# AR_-_Attack_Release.net
KiCad netlist of a schematic drawn in EAGLE
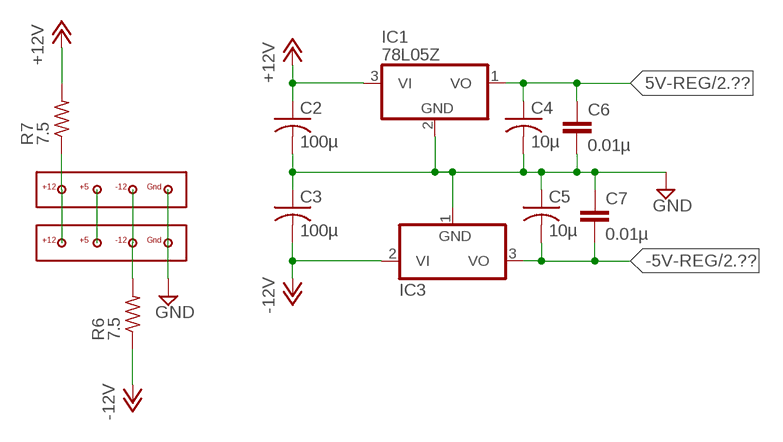
[diagram p0: schematic, sheet 1]
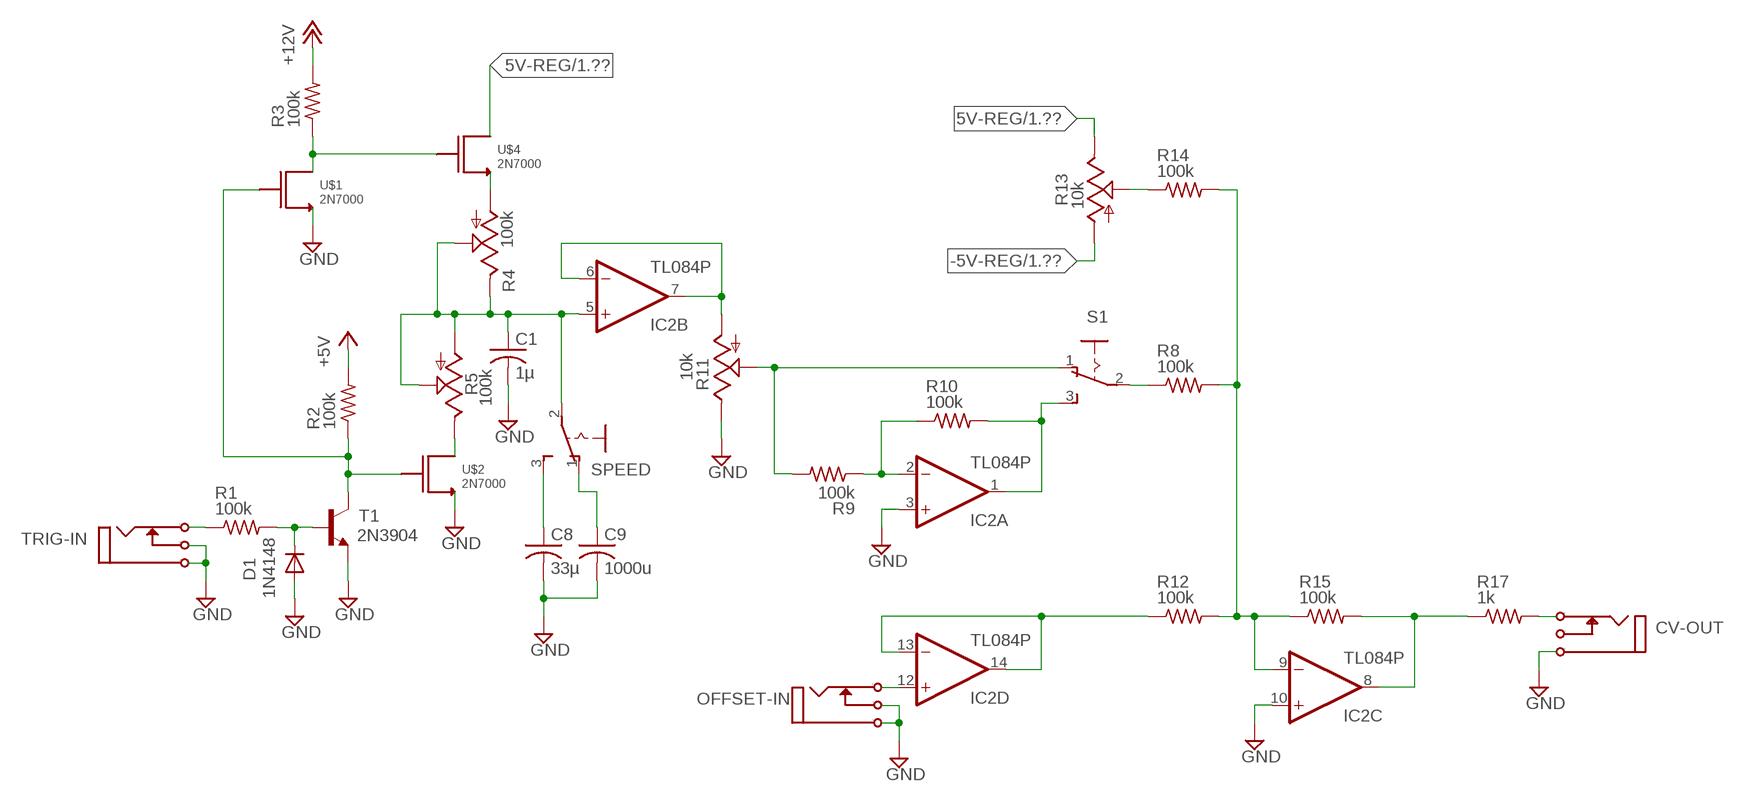
[diagram p1: schematic, sheet 2]
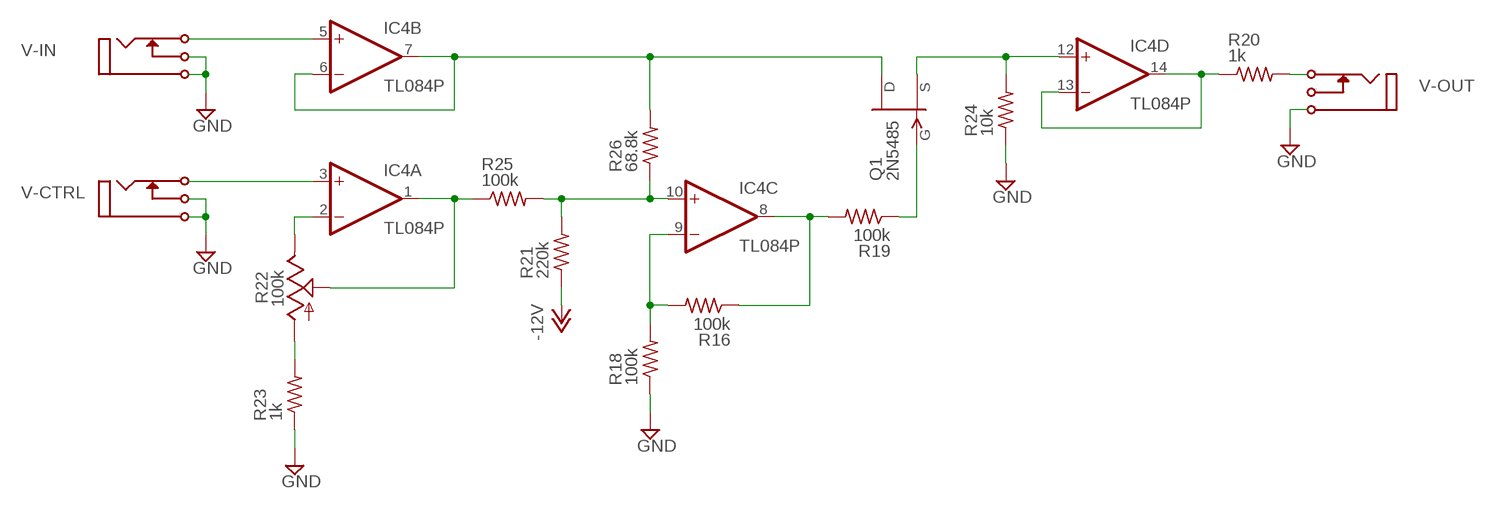
[diagram p2: schematic, sheet 3]

(export (version "E")
  (design (tool "Eeschema 10.0.6"))
  (components
    (comp (ref "C2")
      (value "100µ")
      (footprint "eagle-import:C025-050X050")
      (libsource (lib "eagle-import") (part "C-US025-050X050"))
    )
    (comp (ref "C3")
      (value "100µ")
      (footprint "eagle-import:C025-050X050")
      (libsource (lib "eagle-import") (part "C-US025-050X050"))
    )
    (comp (ref "C4")
      (value "10µ")
      (footprint "eagle-import:C025-050X050")
      (libsource (lib "eagle-import") (part "C-US025-050X050"))
    )
    (comp (ref "C5")
      (value "10µ")
      (footprint "eagle-import:C025-050X050")
      (libsource (lib "eagle-import") (part "C-US025-050X050"))
    )
    (comp (ref "C6")
      (value "0.01µ")
      (footprint "eagle-import:C2.5-2")
      (libsource (lib "eagle-import") (part "C2.5/2"))
    )
    (comp (ref "C7")
      (value "0.01µ")
      (footprint "eagle-import:C2.5-2")
      (libsource (lib "eagle-import") (part "C2.5/2"))
    )
    (comp (ref "IC1")
      (value "78L05Z")
      (footprint "eagle-import:TO92")
      (libsource (lib "eagle-import") (part "78ZL05"))
    )
    (comp (ref "IC3")
      (value "79L05Z")
      (footprint "eagle-import:TO92")
      (libsource (lib "eagle-import") (part "79ZL05"))
    )
    (comp (ref "R6")
      (value "7.5")
      (footprint "eagle-import:0204_7")
      (libsource (lib "eagle-import") (part "R-US_0204/7"))
    )
    (comp (ref "R7")
      (value "7.5")
      (footprint "eagle-import:0204_7")
      (libsource (lib "eagle-import") (part "R-US_0204/7"))
    )
    (comp (ref "U$3")
      (value "POWER_CONNECTOR_4_RGBB")
      (footprint "eagle-import:POWER_CONNECTOR_4_RGBB")
      (libsource (lib "eagle-import") (part "POWER_CONNECTOR_4_RGBB"))
    )
    (comp (ref "U$7")
      (value "POWER_CONNECTOR_4_RGBB")
      (footprint "eagle-import:POWER_CONNECTOR_4_RGBB")
      (libsource (lib "eagle-import") (part "POWER_CONNECTOR_4_RGBB"))
    )
    (comp (ref "IC4")
      (value "TL084P")
      (footprint "eagle-import:DIL14")
      (libsource (lib "eagle-import") (part "TL084P"))
    )
    (comp (ref "Q1")
      (value "2N5485")
      (footprint "eagle-import:TO92-")
      (libsource (lib "eagle-import") (part "?5482N5"))
    )
    (comp (ref "R16")
      (value "100k")
      (footprint "eagle-import:0204_7")
      (libsource (lib "eagle-import") (part "R-US_0204/7"))
    )
    (comp (ref "R18")
      (value "100k")
      (footprint "eagle-import:0204_7")
      (libsource (lib "eagle-import") (part "R-US_0204/7"))
    )
    (comp (ref "R19")
      (value "100k")
      (footprint "eagle-import:0204_7")
      (libsource (lib "eagle-import") (part "R-US_0204/7"))
    )
    (comp (ref "R20")
      (value "1k")
      (footprint "eagle-import:0204_7")
      (libsource (lib "eagle-import") (part "R-US_0204/7"))
    )
    (comp (ref "R21")
      (value "220k")
      (footprint "eagle-import:0204_7")
      (libsource (lib "eagle-import") (part "R-US_0204/7"))
    )
    (comp (ref "R22")
      (value "100k")
      (footprint "eagle-import:B64Y")
      (libsource (lib "eagle-import") (part "TRIM_US-B64Y"))
    )
    (comp (ref "R23")
      (value "1k")
      (footprint "eagle-import:0204_7")
      (libsource (lib "eagle-import") (part "R-US_0204/7"))
    )
    (comp (ref "R24")
      (value "10k")
      (footprint "eagle-import:0204_7")
      (libsource (lib "eagle-import") (part "R-US_0204/7"))
    )
    (comp (ref "R25")
      (value "100k")
      (footprint "eagle-import:0204_7")
      (libsource (lib "eagle-import") (part "R-US_0204/7"))
    )
    (comp (ref "R26")
      (value "68.8k")
      (footprint "eagle-import:0204_7")
      (libsource (lib "eagle-import") (part "R-US_0204/7"))
    )
    (comp (ref "V-CTRL")
      (value "I/O")
      (footprint "eagle-import:MONO_JACK")
      (libsource (lib "eagle-import") (part "MONO_JACK"))
    )
    (comp (ref "V-IN")
      (value "I/O")
      (footprint "eagle-import:MONO_JACK")
      (libsource (lib "eagle-import") (part "MONO_JACK"))
    )
    (comp (ref "V-OUT")
      (value "I/O")
      (footprint "eagle-import:MONO_JACK")
      (libsource (lib "eagle-import") (part "MONO_JACK"))
    )
    (comp (ref "C1")
      (value "1µ")
      (footprint "eagle-import:C025-050X050")
      (libsource (lib "eagle-import") (part "C-US025-050X050"))
    )
    (comp (ref "C8")
      (value "33µ")
      (footprint "eagle-import:C025-050X050")
      (libsource (lib "eagle-import") (part "C-US025-050X050"))
    )
    (comp (ref "C9")
      (value "1000u")
      (footprint "eagle-import:C025-050X050")
      (libsource (lib "eagle-import") (part "C-US025-050X050"))
    )
    (comp (ref "CV-OUT")
      (value "I/O")
      (footprint "eagle-import:MONO_JACK")
      (libsource (lib "eagle-import") (part "MONO_JACK"))
    )
    (comp (ref "D1")
      (value "1N4148")
      (footprint "eagle-import:DO35-7")
      (libsource (lib "eagle-import") (part "1N4148DO35-7"))
    )
    (comp (ref "IC2")
      (value "TL084P")
      (footprint "eagle-import:DIL14")
      (libsource (lib "eagle-import") (part "TL084P"))
    )
    (comp (ref "OFFSET-IN")
      (value "I/O")
      (footprint "eagle-import:MONO_JACK")
      (libsource (lib "eagle-import") (part "MONO_JACK"))
    )
    (comp (ref "R1")
      (value "100k")
      (footprint "eagle-import:0204_7")
      (libsource (lib "eagle-import") (part "R-US_0204/7"))
    )
    (comp (ref "R2")
      (value "100k")
      (footprint "eagle-import:0204_7")
      (libsource (lib "eagle-import") (part "R-US_0204/7"))
    )
    (comp (ref "R3")
      (value "100k")
      (footprint "eagle-import:0204_7")
      (libsource (lib "eagle-import") (part "R-US_0204/7"))
    )
    (comp (ref "R4")
      (value "100k")
      (footprint "eagle-import:B64Y")
      (libsource (lib "eagle-import") (part "TRIM_US-B64Y"))
    )
    (comp (ref "R5")
      (value "100k")
      (footprint "eagle-import:B64Y")
      (libsource (lib "eagle-import") (part "TRIM_US-B64Y"))
    )
    (comp (ref "R8")
      (value "100k")
      (footprint "eagle-import:0204_7")
      (libsource (lib "eagle-import") (part "R-US_0204/7"))
    )
    (comp (ref "R9")
      (value "100k")
      (footprint "eagle-import:0204_7")
      (libsource (lib "eagle-import") (part "R-US_0204/7"))
    )
    (comp (ref "R10")
      (value "100k")
      (footprint "eagle-import:0204_7")
      (libsource (lib "eagle-import") (part "R-US_0204/7"))
    )
    (comp (ref "R11")
      (value "10k")
      (footprint "eagle-import:B64Y")
      (libsource (lib "eagle-import") (part "TRIM_US-B64Y"))
    )
    (comp (ref "R12")
      (value "100k")
      (footprint "eagle-import:0204_7")
      (libsource (lib "eagle-import") (part "R-US_0204/7"))
    )
    (comp (ref "R13")
      (value "10k")
      (footprint "eagle-import:B64Y")
      (libsource (lib "eagle-import") (part "TRIM_US-B64Y"))
    )
    (comp (ref "R14")
      (value "100k")
      (footprint "eagle-import:0204_7")
      (libsource (lib "eagle-import") (part "R-US_0204/7"))
    )
    (comp (ref "R15")
      (value "100k")
      (footprint "eagle-import:0204_7")
      (libsource (lib "eagle-import") (part "R-US_0204/7"))
    )
    (comp (ref "R17")
      (value "1k")
      (footprint "eagle-import:0204_7")
      (libsource (lib "eagle-import") (part "R-US_0204/7"))
    )
    (comp (ref "S1")
      (value "255SB")
      (footprint "eagle-import:255SB")
      (libsource (lib "eagle-import") (part "255SB"))
    )
    (comp (ref "SPEED")
      (value "255SB")
      (footprint "eagle-import:255SB")
      (libsource (lib "eagle-import") (part "255SB"))
    )
    (comp (ref "T1")
      (value "2N3904")
      (footprint "eagle-import:TO92")
      (libsource (lib "eagle-import") (part "2N3904"))
    )
    (comp (ref "TRIG-IN")
      (value "I/O")
      (footprint "eagle-import:MONO_JACK")
      (libsource (lib "eagle-import") (part "MONO_JACK"))
    )
    (comp (ref "U$1")
      (value "2N7000")
      (footprint "eagle-import:2N7000")
      (libsource (lib "eagle-import") (part "2N7000"))
    )
    (comp (ref "U$2")
      (value "2N7000")
      (footprint "eagle-import:2N7000")
      (libsource (lib "eagle-import") (part "2N7000"))
    )
    (comp (ref "U$4")
      (value "2N7000")
      (footprint "eagle-import:2N7000")
      (libsource (lib "eagle-import") (part "2N7000"))
    )
  )
  (nets
    (net (code "1") (name "+5V") (class "Default")
      (node (ref "R2") (pin "2") (pinfunction "2_2") (pintype "passive"))
    )
    (net (code "2") (name "+12V") (class "Default")
      (node (ref "C2") (pin "1") (pinfunction "1_1") (pintype "passive"))
      (node (ref "IC1") (pin "3") (pinfunction "VI_3") (pintype "input"))
      (node (ref "R3") (pin "2") (pinfunction "2_2") (pintype "passive"))
      (node (ref "R7") (pin "2") (pinfunction "2_2") (pintype "passive"))
    )
    (net (code "3") (name "-5V-REG") (class "Default")
      (node (ref "C5") (pin "2") (pinfunction "2_2") (pintype "passive"))
      (node (ref "C7") (pin "2") (pinfunction "2_2") (pintype "passive"))
      (node (ref "IC3") (pin "3") (pinfunction "VO_3") (pintype "passive"))
      (node (ref "R13") (pin "A") (pinfunction "A_A") (pintype "passive"))
    )
    (net (code "4") (name "-12V") (class "Default")
      (node (ref "C3") (pin "2") (pinfunction "2_2") (pintype "passive"))
      (node (ref "IC3") (pin "2") (pinfunction "VI_2") (pintype "input"))
      (node (ref "R21") (pin "1") (pinfunction "1_1") (pintype "passive"))
      (node (ref "R6") (pin "1") (pinfunction "1_1") (pintype "passive"))
    )
    (net (code "5") (name "5V-REG") (class "Default")
      (node (ref "C4") (pin "1") (pinfunction "1_1") (pintype "passive"))
      (node (ref "C6") (pin "1") (pinfunction "1_1") (pintype "passive"))
      (node (ref "IC1") (pin "1") (pinfunction "VO_1") (pintype "passive"))
      (node (ref "R13") (pin "E") (pinfunction "E_E") (pintype "passive"))
      (node (ref "U$4") (pin "D") (pinfunction "D_D") (pintype "bidirectional"))
    )
    (net (code "6") (name "GND") (class "Default")
      (node (ref "C1") (pin "2") (pinfunction "2_2") (pintype "passive"))
      (node (ref "C2") (pin "2") (pinfunction "2_2") (pintype "passive"))
      (node (ref "C3") (pin "1") (pinfunction "1_1") (pintype "passive"))
      (node (ref "C4") (pin "2") (pinfunction "2_2") (pintype "passive"))
      (node (ref "C5") (pin "1") (pinfunction "1_1") (pintype "passive"))
      (node (ref "C6") (pin "2") (pinfunction "2_2") (pintype "passive"))
      (node (ref "C7") (pin "1") (pinfunction "1_1") (pintype "passive"))
      (node (ref "C8") (pin "2") (pinfunction "2_2") (pintype "passive"))
      (node (ref "C9") (pin "2") (pinfunction "2_2") (pintype "passive"))
      (node (ref "CV-OUT") (pin "P$1") (pinfunction "P$1_P$1") (pintype "bidirectional"))
      (node (ref "D1") (pin "A") (pinfunction "A_A") (pintype "passive"))
      (node (ref "IC1") (pin "2") (pinfunction "GND_2") (pintype "passive"))
      (node (ref "IC2") (pin "10") (pinfunction "+IN_10") (pintype "input"))
      (node (ref "IC2") (pin "3") (pinfunction "+IN_3") (pintype "input"))
      (node (ref "IC3") (pin "1") (pinfunction "GND_1") (pintype "passive"))
      (node (ref "OFFSET-IN") (pin "P$1") (pinfunction "P$1_P$1") (pintype "bidirectional"))
      (node (ref "OFFSET-IN") (pin "P$3") (pinfunction "P3_P$3") (pintype "bidirectional"))
      (node (ref "R11") (pin "E") (pinfunction "E_E") (pintype "passive"))
      (node (ref "R18") (pin "1") (pinfunction "1_1") (pintype "passive"))
      (node (ref "R23") (pin "1") (pinfunction "1_1") (pintype "passive"))
      (node (ref "R24") (pin "1") (pinfunction "1_1") (pintype "passive"))
      (node (ref "T1") (pin "3") (pinfunction "E_3") (pintype "passive"))
      (node (ref "TRIG-IN") (pin "P$1") (pinfunction "P$1_P$1") (pintype "bidirectional"))
      (node (ref "TRIG-IN") (pin "P$3") (pinfunction "P3_P$3") (pintype "bidirectional"))
      (node (ref "U$1") (pin "S") (pinfunction "S_S") (pintype "bidirectional"))
      (node (ref "U$2") (pin "S") (pinfunction "S_S") (pintype "bidirectional"))
      (node (ref "U$3") (pin "GND") (pinfunction "GND_GND") (pintype "bidirectional"))
      (node (ref "U$7") (pin "GND") (pinfunction "GND_GND") (pintype "bidirectional"))
      (node (ref "V-CTRL") (pin "P$1") (pinfunction "P$1_P$1") (pintype "bidirectional"))
      (node (ref "V-CTRL") (pin "P$3") (pinfunction "P3_P$3") (pintype "bidirectional"))
      (node (ref "V-IN") (pin "P$1") (pinfunction "P$1_P$1") (pintype "bidirectional"))
      (node (ref "V-IN") (pin "P$3") (pinfunction "P3_P$3") (pintype "bidirectional"))
      (node (ref "V-OUT") (pin "P$1") (pinfunction "P$1_P$1") (pintype "bidirectional"))
    )
    (net (code "7") (name "Net-(CV-OUT-P2)") (class "Default")
      (node (ref "CV-OUT") (pin "P$2") (pinfunction "P2_P$2") (pintype "bidirectional"))
      (node (ref "R17") (pin "2") (pinfunction "2_2") (pintype "passive"))
    )
    (net (code "8") (name "Net-(IC2A--IN)") (class "Default")
      (node (ref "IC2") (pin "2") (pinfunction "-IN_2") (pintype "input"))
      (node (ref "R10") (pin "1") (pinfunction "1_1") (pintype "passive"))
      (node (ref "R9") (pin "1") (pinfunction "1_1") (pintype "passive"))
    )
    (net (code "9") (name "Net-(IC2A-OUT)") (class "Default")
      (node (ref "IC2") (pin "1") (pinfunction "OUT_1") (pintype "output"))
      (node (ref "R10") (pin "2") (pinfunction "2_2") (pintype "passive"))
      (node (ref "S1") (pin "3") (pinfunction "S_3") (pintype "passive"))
    )
    (net (code "10") (name "Net-(IC2B-+IN)") (class "Default")
      (node (ref "C1") (pin "1") (pinfunction "1_1") (pintype "passive"))
      (node (ref "IC2") (pin "5") (pinfunction "+IN_5") (pintype "input"))
      (node (ref "R4") (pin "E") (pinfunction "E_E") (pintype "passive"))
      (node (ref "R4") (pin "S") (pinfunction "S_S") (pintype "passive"))
      (node (ref "R5") (pin "A") (pinfunction "A_A") (pintype "passive"))
      (node (ref "R5") (pin "S") (pinfunction "S_S") (pintype "passive"))
      (node (ref "SPEED") (pin "2") (pinfunction "P_2") (pintype "passive"))
    )
    (net (code "11") (name "Net-(IC2B--IN)") (class "Default")
      (node (ref "IC2") (pin "6") (pinfunction "-IN_6") (pintype "input"))
      (node (ref "IC2") (pin "7") (pinfunction "OUT_7") (pintype "output"))
      (node (ref "R11") (pin "A") (pinfunction "A_A") (pintype "passive"))
    )
    (net (code "12") (name "Net-(IC2C--IN)") (class "Default")
      (node (ref "IC2") (pin "9") (pinfunction "-IN_9") (pintype "input"))
      (node (ref "R12") (pin "2") (pinfunction "2_2") (pintype "passive"))
      (node (ref "R14") (pin "2") (pinfunction "2_2") (pintype "passive"))
      (node (ref "R15") (pin "1") (pinfunction "1_1") (pintype "passive"))
      (node (ref "R8") (pin "2") (pinfunction "2_2") (pintype "passive"))
    )
    (net (code "13") (name "Net-(IC2C-OUT)") (class "Default")
      (node (ref "IC2") (pin "8") (pinfunction "OUT_8") (pintype "output"))
      (node (ref "R15") (pin "2") (pinfunction "2_2") (pintype "passive"))
      (node (ref "R17") (pin "1") (pinfunction "1_1") (pintype "passive"))
    )
    (net (code "14") (name "Net-(IC2D-+IN)") (class "Default")
      (node (ref "IC2") (pin "12") (pinfunction "+IN_12") (pintype "input"))
      (node (ref "OFFSET-IN") (pin "P$2") (pinfunction "P2_P$2") (pintype "bidirectional"))
    )
    (net (code "15") (name "Net-(IC2D--IN)") (class "Default")
      (node (ref "IC2") (pin "13") (pinfunction "-IN_13") (pintype "input"))
      (node (ref "IC2") (pin "14") (pinfunction "OUT_14") (pintype "output"))
      (node (ref "R12") (pin "1") (pinfunction "1_1") (pintype "passive"))
    )
    (net (code "16") (name "Net-(IC4A-+IN)") (class "Default")
      (node (ref "IC4") (pin "3") (pinfunction "+IN_3") (pintype "input"))
      (node (ref "V-CTRL") (pin "P$2") (pinfunction "P2_P$2") (pintype "bidirectional"))
    )
    (net (code "17") (name "Net-(IC4A--IN)") (class "Default")
      (node (ref "IC4") (pin "2") (pinfunction "-IN_2") (pintype "input"))
      (node (ref "R22") (pin "E") (pinfunction "E_E") (pintype "passive"))
    )
    (net (code "18") (name "Net-(IC4A-OUT)") (class "Default")
      (node (ref "IC4") (pin "1") (pinfunction "OUT_1") (pintype "output"))
      (node (ref "R22") (pin "S") (pinfunction "S_S") (pintype "passive"))
      (node (ref "R25") (pin "1") (pinfunction "1_1") (pintype "passive"))
    )
    (net (code "19") (name "Net-(IC4B-+IN)") (class "Default")
      (node (ref "IC4") (pin "5") (pinfunction "+IN_5") (pintype "input"))
      (node (ref "V-IN") (pin "P$2") (pinfunction "P2_P$2") (pintype "bidirectional"))
    )
    (net (code "20") (name "Net-(IC4B--IN)") (class "Default")
      (node (ref "IC4") (pin "6") (pinfunction "-IN_6") (pintype "input"))
      (node (ref "IC4") (pin "7") (pinfunction "OUT_7") (pintype "output"))
      (node (ref "Q1") (pin "3") (pinfunction "D_3") (pintype "passive"))
      (node (ref "R26") (pin "2") (pinfunction "2_2") (pintype "passive"))
    )
    (net (code "21") (name "Net-(IC4C-+IN)") (class "Default")
      (node (ref "IC4") (pin "10") (pinfunction "+IN_10") (pintype "input"))
      (node (ref "R21") (pin "2") (pinfunction "2_2") (pintype "passive"))
      (node (ref "R25") (pin "2") (pinfunction "2_2") (pintype "passive"))
      (node (ref "R26") (pin "1") (pinfunction "1_1") (pintype "passive"))
    )
    (net (code "22") (name "Net-(IC4C--IN)") (class "Default")
      (node (ref "IC4") (pin "9") (pinfunction "-IN_9") (pintype "input"))
      (node (ref "R16") (pin "2") (pinfunction "2_2") (pintype "passive"))
      (node (ref "R18") (pin "2") (pinfunction "2_2") (pintype "passive"))
    )
    (net (code "23") (name "Net-(IC4C-OUT)") (class "Default")
      (node (ref "IC4") (pin "8") (pinfunction "OUT_8") (pintype "output"))
      (node (ref "R16") (pin "1") (pinfunction "1_1") (pintype "passive"))
      (node (ref "R19") (pin "2") (pinfunction "2_2") (pintype "passive"))
    )
    (net (code "24") (name "Net-(IC4D-+IN)") (class "Default")
      (node (ref "IC4") (pin "12") (pinfunction "+IN_12") (pintype "input"))
      (node (ref "Q1") (pin "2") (pinfunction "S_2") (pintype "passive"))
      (node (ref "R24") (pin "2") (pinfunction "2_2") (pintype "passive"))
    )
    (net (code "25") (name "Net-(IC4D--IN)") (class "Default")
      (node (ref "IC4") (pin "13") (pinfunction "-IN_13") (pintype "input"))
      (node (ref "IC4") (pin "14") (pinfunction "OUT_14") (pintype "output"))
      (node (ref "R20") (pin "1") (pinfunction "1_1") (pintype "passive"))
    )
    (net (code "26") (name "Net-(Q1-G)") (class "Default")
      (node (ref "Q1") (pin "1") (pinfunction "G_1") (pintype "passive"))
      (node (ref "R19") (pin "1") (pinfunction "1_1") (pintype "passive"))
    )
    (net (code "27") (name "Net-(R3-Pad1)") (class "Default")
      (node (ref "R3") (pin "1") (pinfunction "1_1") (pintype "passive"))
      (node (ref "U$1") (pin "D") (pinfunction "D_D") (pintype "bidirectional"))
      (node (ref "U$4") (pin "G") (pinfunction "G_G") (pintype "bidirectional"))
    )
    (net (code "28") (name "Net-(R4-PadA)") (class "Default")
      (node (ref "R4") (pin "A") (pinfunction "A_A") (pintype "passive"))
      (node (ref "U$4") (pin "S") (pinfunction "S_S") (pintype "bidirectional"))
    )
    (net (code "29") (name "Net-(R5-PadE)") (class "Default")
      (node (ref "R5") (pin "E") (pinfunction "E_E") (pintype "passive"))
      (node (ref "U$2") (pin "D") (pinfunction "D_D") (pintype "bidirectional"))
    )
    (net (code "30") (name "Net-(R6-Pad2)") (class "Default")
      (node (ref "R6") (pin "2") (pinfunction "2_2") (pintype "passive"))
      (node (ref "U$3") (pin "-12") (pinfunction "-12_-12") (pintype "bidirectional"))
      (node (ref "U$7") (pin "-12") (pinfunction "-12_-12") (pintype "bidirectional"))
    )
    (net (code "31") (name "Net-(R7-Pad1)") (class "Default")
      (node (ref "R7") (pin "1") (pinfunction "1_1") (pintype "passive"))
      (node (ref "U$3") (pin "+12") (pinfunction "+12_+12") (pintype "bidirectional"))
      (node (ref "U$7") (pin "+12") (pinfunction "+12_+12") (pintype "bidirectional"))
    )
    (net (code "32") (name "Net-(R13-PadS)") (class "Default")
      (node (ref "R13") (pin "S") (pinfunction "S_S") (pintype "passive"))
      (node (ref "R14") (pin "1") (pinfunction "1_1") (pintype "passive"))
    )
    (net (code "33") (name "Net-(R22-PadA)") (class "Default")
      (node (ref "R22") (pin "A") (pinfunction "A_A") (pintype "passive"))
      (node (ref "R23") (pin "2") (pinfunction "2_2") (pintype "passive"))
    )
    (net (code "34") (name "Net-(S1-O)") (class "Default")
      (node (ref "R11") (pin "S") (pinfunction "S_S") (pintype "passive"))
      (node (ref "R9") (pin "2") (pinfunction "2_2") (pintype "passive"))
      (node (ref "S1") (pin "1") (pinfunction "O_1") (pintype "passive"))
    )
    (net (code "35") (name "Net-(S1-P)") (class "Default")
      (node (ref "R8") (pin "1") (pinfunction "1_1") (pintype "passive"))
      (node (ref "S1") (pin "2") (pinfunction "P_2") (pintype "passive"))
    )
    (net (code "36") (name "Net-(SPEED-O)") (class "Default")
      (node (ref "C9") (pin "1") (pinfunction "1_1") (pintype "passive"))
      (node (ref "SPEED") (pin "1") (pinfunction "O_1") (pintype "passive"))
    )
    (net (code "37") (name "Net-(SPEED-S)") (class "Default")
      (node (ref "C8") (pin "1") (pinfunction "1_1") (pintype "passive"))
      (node (ref "SPEED") (pin "3") (pinfunction "S_3") (pintype "passive"))
    )
    (net (code "38") (name "Net-(T1-B)") (class "Default")
      (node (ref "D1") (pin "C") (pinfunction "C_C") (pintype "passive"))
      (node (ref "R1") (pin "2") (pinfunction "2_2") (pintype "passive"))
      (node (ref "T1") (pin "2") (pinfunction "B_2") (pintype "passive"))
    )
    (net (code "39") (name "Net-(T1-C)") (class "Default")
      (node (ref "R2") (pin "1") (pinfunction "1_1") (pintype "passive"))
      (node (ref "T1") (pin "1") (pinfunction "C_1") (pintype "passive"))
      (node (ref "U$1") (pin "G") (pinfunction "G_G") (pintype "bidirectional"))
      (node (ref "U$2") (pin "G") (pinfunction "G_G") (pintype "bidirectional"))
    )
    (net (code "40") (name "Net-(TRIG-IN-P2)") (class "Default")
      (node (ref "R1") (pin "1") (pinfunction "1_1") (pintype "passive"))
      (node (ref "TRIG-IN") (pin "P$2") (pinfunction "P2_P$2") (pintype "bidirectional"))
    )
    (net (code "41") (name "Net-(U$3-Pad+5)") (class "Default")
      (node (ref "U$3") (pin "+5") (pinfunction "+5_+5") (pintype "bidirectional"))
      (node (ref "U$7") (pin "+5") (pinfunction "+5_+5") (pintype "bidirectional"))
    )
    (net (code "42") (name "Net-(V-OUT-P2)") (class "Default")
      (node (ref "R20") (pin "2") (pinfunction "2_2") (pintype "passive"))
      (node (ref "V-OUT") (pin "P$2") (pinfunction "P2_P$2") (pintype "bidirectional"))
    )
    (net (code "43") (name "unconnected-(CV-OUT-P3-PadP$3)") (class "Default")
      (node (ref "CV-OUT") (pin "P$3") (pinfunction "P3_P$3") (pintype "bidirectional"))
    )
    (net (code "44") (name "unconnected-(V-OUT-P3-PadP$3)") (class "Default")
      (node (ref "V-OUT") (pin "P$3") (pinfunction "P3_P$3") (pintype "bidirectional"))
    )
  )
)
